# shared_pcb.net
KiCad netlist of a schematic drawn in EAGLE
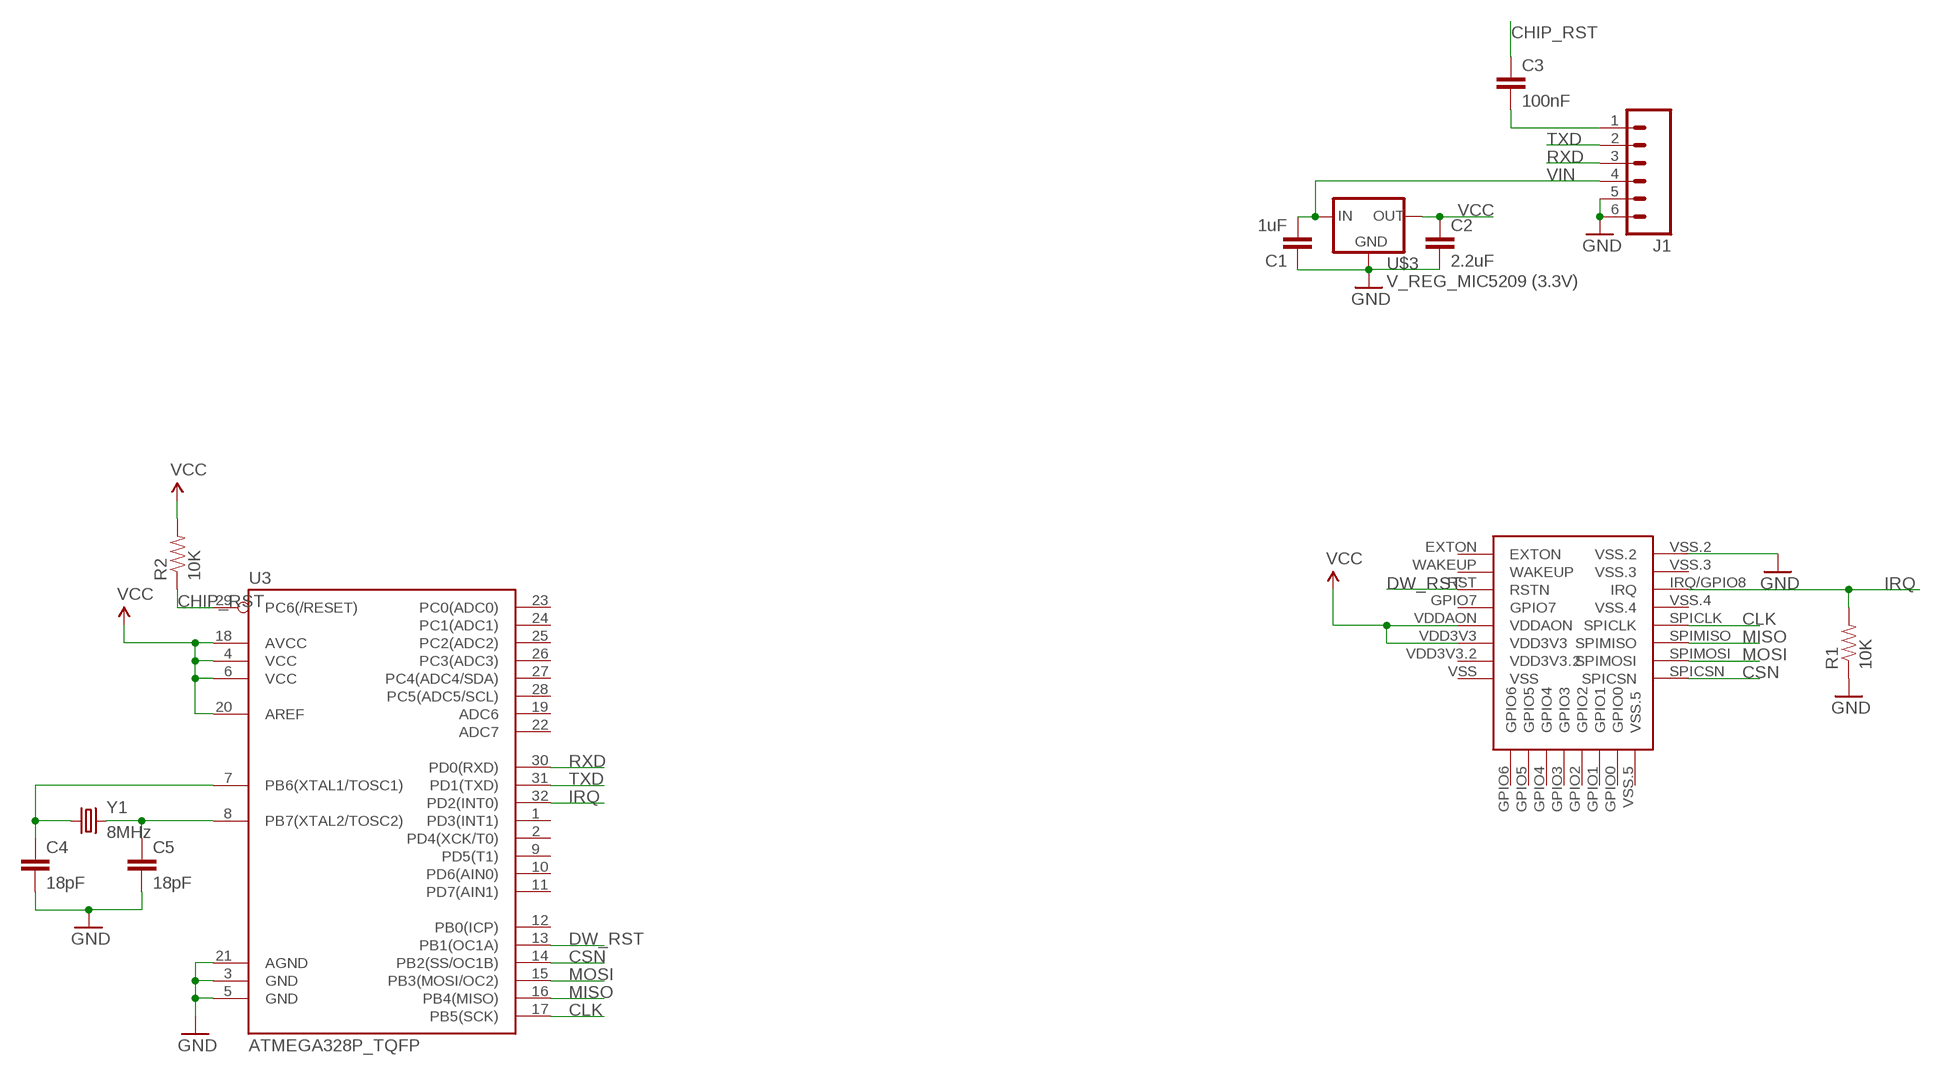
[diagram p0: schematic, sheet 1]

(export (version "E")
  (design (tool "Eeschema 10.0.6"))
  (components
    (comp (ref "C1")
      (value "1uF")
      (footprint "eagle-import:1206")
      (libsource (lib "eagle-import") (part "CAP1206"))
    )
    (comp (ref "C2")
      (value "2.2uF")
      (footprint "eagle-import:1206")
      (libsource (lib "eagle-import") (part "CAP1206"))
    )
    (comp (ref "C3")
      (value "100nF")
      (footprint "eagle-import:1206")
      (libsource (lib "eagle-import") (part "CAP1206"))
    )
    (comp (ref "C4")
      (value "18pF")
      (footprint "eagle-import:1206")
      (libsource (lib "eagle-import") (part "CAP1206"))
    )
    (comp (ref "C5")
      (value "18pF")
      (footprint "eagle-import:1206")
      (libsource (lib "eagle-import") (part "CAP1206"))
    )
    (comp (ref "J1")
      (value "M06LOCK")
      (footprint "eagle-import:1X06_LOCK")
      (libsource (lib "eagle-import") (part "M06LOCK"))
    )
    (comp (ref "R1")
      (value "10K")
      (footprint "eagle-import:1206")
      (libsource (lib "eagle-import") (part "RESISTOR1206"))
    )
    (comp (ref "R2")
      (value "10K")
      (footprint "eagle-import:1206")
      (libsource (lib "eagle-import") (part "RESISTOR1206"))
    )
    (comp (ref "U$1")
      (value "DWM1000")
      (footprint "eagle-import:DWM1000")
      (libsource (lib "eagle-import") (part "DWM1000"))
    )
    (comp (ref "U$3")
      (value "V_REG_MIC5209 (3.3V)")
      (footprint "eagle-import:SOT223")
      (libsource (lib "eagle-import") (part "V_REG_MIC2920"))
    )
    (comp (ref "U3")
      (value "ATMEGA328P_TQFP")
      (footprint "eagle-import:TQFP32-08")
      (libsource (lib "eagle-import") (part "ATMEGA328P_TQFP"))
    )
    (comp (ref "Y1")
      (value "8MHz")
      (footprint "eagle-import:CRYSTAL-TXC-7A")
      (libsource (lib "eagle-import") (part "CRYSTALTXC-7A"))
    )
  )
  (nets
    (net (code "1") (name "/CHIP_RST") (class "Default")
      (node (ref "C3") (pin "1") (pinfunction "1_1") (pintype "passive"))
      (node (ref "R2") (pin "1") (pinfunction "1_1") (pintype "passive"))
      (node (ref "U3") (pin "29") (pinfunction "PC6(/RESET)_29") (pintype "bidirectional"))
    )
    (net (code "2") (name "/CLK") (class "Default")
      (node (ref "U$1") (pin "SPICLK") (pinfunction "SPICLK_SPICLK") (pintype "bidirectional"))
      (node (ref "U3") (pin "17") (pinfunction "PB5(SCK)_17") (pintype "bidirectional"))
    )
    (net (code "3") (name "/CSN") (class "Default")
      (node (ref "U$1") (pin "SPICSN") (pinfunction "SPICSN_SPICSN") (pintype "bidirectional"))
      (node (ref "U3") (pin "14") (pinfunction "PB2(SS/OC1B)_14") (pintype "bidirectional"))
    )
    (net (code "4") (name "/DW_RST") (class "Default")
      (node (ref "U$1") (pin "RST") (pinfunction "RSTN_RST") (pintype "bidirectional"))
      (node (ref "U3") (pin "13") (pinfunction "PB1(OC1A)_13") (pintype "bidirectional"))
    )
    (net (code "5") (name "/IRQ") (class "Default")
      (node (ref "R1") (pin "2") (pinfunction "2_2") (pintype "passive"))
      (node (ref "U$1") (pin "IRQ/GPIO8") (pinfunction "IRQ_IRQ/GPIO8") (pintype "bidirectional"))
      (node (ref "U3") (pin "32") (pinfunction "PD2(INT0)_32") (pintype "bidirectional"))
    )
    (net (code "6") (name "/MISO") (class "Default")
      (node (ref "U$1") (pin "SPIMISO") (pinfunction "SPIMISO_SPIMISO") (pintype "bidirectional"))
      (node (ref "U3") (pin "16") (pinfunction "PB4(MISO)_16") (pintype "bidirectional"))
    )
    (net (code "7") (name "/MOSI") (class "Default")
      (node (ref "U$1") (pin "SPIMOSI") (pinfunction "SPIMOSI_SPIMOSI") (pintype "bidirectional"))
      (node (ref "U3") (pin "15") (pinfunction "PB3(MOSI/OC2)_15") (pintype "bidirectional"))
    )
    (net (code "8") (name "/RXD") (class "Default")
      (node (ref "J1") (pin "3") (pinfunction "3_3") (pintype "passive"))
      (node (ref "U3") (pin "30") (pinfunction "PD0(RXD)_30") (pintype "bidirectional"))
    )
    (net (code "9") (name "/TXD") (class "Default")
      (node (ref "J1") (pin "2") (pinfunction "2_2") (pintype "passive"))
      (node (ref "U3") (pin "31") (pinfunction "PD1(TXD)_31") (pintype "bidirectional"))
    )
    (net (code "10") (name "/VIN") (class "Default")
      (node (ref "C1") (pin "2") (pinfunction "2_2") (pintype "passive"))
      (node (ref "J1") (pin "4") (pinfunction "4_4") (pintype "passive"))
      (node (ref "U$3") (pin "1") (pinfunction "IN_1") (pintype "input"))
    )
    (net (code "11") (name "GND") (class "Default")
      (node (ref "C1") (pin "1") (pinfunction "1_1") (pintype "passive"))
      (node (ref "C2") (pin "2") (pinfunction "2_2") (pintype "passive"))
      (node (ref "C4") (pin "2") (pinfunction "2_2") (pintype "passive"))
      (node (ref "C5") (pin "2") (pinfunction "2_2") (pintype "passive"))
      (node (ref "J1") (pin "5") (pinfunction "5_5") (pintype "passive"))
      (node (ref "J1") (pin "6") (pinfunction "6_6") (pintype "passive"))
      (node (ref "R1") (pin "1") (pinfunction "1_1") (pintype "passive"))
      (node (ref "U$1") (pin "VSS.2") (pinfunction "VSS.2_VSS.2") (pintype "bidirectional"))
      (node (ref "U$3") (pin "2") (pinfunction "GND_2") (pintype "input"))
      (node (ref "U3") (pin "21") (pinfunction "AGND_21") (pintype "bidirectional"))
      (node (ref "U3") (pin "3") (pinfunction "GND_3") (pintype "bidirectional"))
      (node (ref "U3") (pin "5") (pinfunction "GND_5") (pintype "bidirectional"))
    )
    (net (code "12") (name "Net-(C3-Pad2)") (class "Default")
      (node (ref "C3") (pin "2") (pinfunction "2_2") (pintype "passive"))
      (node (ref "J1") (pin "1") (pinfunction "1_1") (pintype "passive"))
    )
    (net (code "13") (name "Net-(U3-PB6(XTAL1{slash}TOSC1))") (class "Default")
      (node (ref "C4") (pin "1") (pinfunction "1_1") (pintype "passive"))
      (node (ref "U3") (pin "7") (pinfunction "PB6(XTAL1/TOSC1)_7") (pintype "bidirectional"))
      (node (ref "Y1") (pin "P$1") (pinfunction "1_P$1") (pintype "passive"))
    )
    (net (code "14") (name "Net-(U3-PB7(XTAL2{slash}TOSC2))") (class "Default")
      (node (ref "C5") (pin "1") (pinfunction "1_1") (pintype "passive"))
      (node (ref "U3") (pin "8") (pinfunction "PB7(XTAL2/TOSC2)_8") (pintype "bidirectional"))
      (node (ref "Y1") (pin "P$2") (pinfunction "2_P$2") (pintype "passive"))
    )
    (net (code "15") (name "VCC") (class "Default")
      (node (ref "C2") (pin "1") (pinfunction "1_1") (pintype "passive"))
      (node (ref "R2") (pin "2") (pinfunction "2_2") (pintype "passive"))
      (node (ref "U$1") (pin "VDD3V3") (pinfunction "VDD3V3_VDD3V3") (pintype "bidirectional"))
      (node (ref "U$1") (pin "VDDAON") (pinfunction "VDDAON_VDDAON") (pintype "bidirectional"))
      (node (ref "U$3") (pin "3") (pinfunction "OUT_3") (pintype "passive"))
      (node (ref "U3") (pin "18") (pinfunction "AVCC_18") (pintype "bidirectional"))
      (node (ref "U3") (pin "20") (pinfunction "AREF_20") (pintype "bidirectional"))
      (node (ref "U3") (pin "4") (pinfunction "VCC_4") (pintype "bidirectional"))
      (node (ref "U3") (pin "6") (pinfunction "VCC_6") (pintype "bidirectional"))
    )
    (net (code "16") (name "unconnected-(U$1-PadEXTON)") (class "Default")
      (node (ref "U$1") (pin "EXTON") (pinfunction "EXTON_EXTON") (pintype "bidirectional"))
    )
    (net (code "17") (name "unconnected-(U$1-PadGPIO0)") (class "Default")
      (node (ref "U$1") (pin "GPIO0") (pinfunction "GPIO0_GPIO0") (pintype "bidirectional"))
    )
    (net (code "18") (name "unconnected-(U$1-PadGPIO1)") (class "Default")
      (node (ref "U$1") (pin "GPIO1") (pinfunction "GPIO1_GPIO1") (pintype "bidirectional"))
    )
    (net (code "19") (name "unconnected-(U$1-PadGPIO2)") (class "Default")
      (node (ref "U$1") (pin "GPIO2") (pinfunction "GPIO2_GPIO2") (pintype "bidirectional"))
    )
    (net (code "20") (name "unconnected-(U$1-PadGPIO3)") (class "Default")
      (node (ref "U$1") (pin "GPIO3") (pinfunction "GPIO3_GPIO3") (pintype "bidirectional"))
    )
    (net (code "21") (name "unconnected-(U$1-PadGPIO4)") (class "Default")
      (node (ref "U$1") (pin "GPIO4") (pinfunction "GPIO4_GPIO4") (pintype "bidirectional"))
    )
    (net (code "22") (name "unconnected-(U$1-PadGPIO5)") (class "Default")
      (node (ref "U$1") (pin "GPIO5") (pinfunction "GPIO5_GPIO5") (pintype "bidirectional"))
    )
    (net (code "23") (name "unconnected-(U$1-PadGPIO6)") (class "Default")
      (node (ref "U$1") (pin "GPIO6") (pinfunction "GPIO6_GPIO6") (pintype "bidirectional"))
    )
    (net (code "24") (name "unconnected-(U$1-PadGPIO7)") (class "Default")
      (node (ref "U$1") (pin "GPIO7") (pinfunction "GPIO7_GPIO7") (pintype "bidirectional"))
    )
    (net (code "25") (name "unconnected-(U$1-PadVDD3V3.2)") (class "Default")
      (node (ref "U$1") (pin "VDD3V3.2") (pinfunction "VDD3V3.2_VDD3V3.2") (pintype "bidirectional"))
    )
    (net (code "26") (name "unconnected-(U$1-PadVSS)") (class "Default")
      (node (ref "U$1") (pin "VSS") (pinfunction "VSS_VSS") (pintype "bidirectional"))
    )
    (net (code "27") (name "unconnected-(U$1-PadVSS.3)") (class "Default")
      (node (ref "U$1") (pin "VSS.3") (pinfunction "VSS.3_VSS.3") (pintype "bidirectional"))
    )
    (net (code "28") (name "unconnected-(U$1-PadVSS.4)") (class "Default")
      (node (ref "U$1") (pin "VSS.4") (pinfunction "VSS.4_VSS.4") (pintype "bidirectional"))
    )
    (net (code "29") (name "unconnected-(U$1-PadVSS.5)") (class "Default")
      (node (ref "U$1") (pin "VSS.5") (pinfunction "VSS.5_VSS.5") (pintype "bidirectional"))
    )
    (net (code "30") (name "unconnected-(U$1-PadWAKEUP)") (class "Default")
      (node (ref "U$1") (pin "WAKEUP") (pinfunction "WAKEUP_WAKEUP") (pintype "bidirectional"))
    )
    (net (code "31") (name "unconnected-(U3-ADC6-Pad19)") (class "Default")
      (node (ref "U3") (pin "19") (pinfunction "ADC6_19") (pintype "bidirectional"))
    )
    (net (code "32") (name "unconnected-(U3-ADC7-Pad22)") (class "Default")
      (node (ref "U3") (pin "22") (pinfunction "ADC7_22") (pintype "bidirectional"))
    )
    (net (code "33") (name "unconnected-(U3-PB0(ICP)-Pad12)") (class "Default")
      (node (ref "U3") (pin "12") (pinfunction "PB0(ICP)_12") (pintype "bidirectional"))
    )
    (net (code "34") (name "unconnected-(U3-PC0(ADC0)-Pad23)") (class "Default")
      (node (ref "U3") (pin "23") (pinfunction "PC0(ADC0)_23") (pintype "bidirectional"))
    )
    (net (code "35") (name "unconnected-(U3-PC1(ADC1)-Pad24)") (class "Default")
      (node (ref "U3") (pin "24") (pinfunction "PC1(ADC1)_24") (pintype "bidirectional"))
    )
    (net (code "36") (name "unconnected-(U3-PC2(ADC2)-Pad25)") (class "Default")
      (node (ref "U3") (pin "25") (pinfunction "PC2(ADC2)_25") (pintype "bidirectional"))
    )
    (net (code "37") (name "unconnected-(U3-PC3(ADC3)-Pad26)") (class "Default")
      (node (ref "U3") (pin "26") (pinfunction "PC3(ADC3)_26") (pintype "bidirectional"))
    )
    (net (code "38") (name "unconnected-(U3-PC4(ADC4{slash}SDA)-Pad27)") (class "Default")
      (node (ref "U3") (pin "27") (pinfunction "PC4(ADC4/SDA)_27") (pintype "bidirectional"))
    )
    (net (code "39") (name "unconnected-(U3-PC5(ADC5{slash}SCL)-Pad28)") (class "Default")
      (node (ref "U3") (pin "28") (pinfunction "PC5(ADC5/SCL)_28") (pintype "bidirectional"))
    )
    (net (code "40") (name "unconnected-(U3-PD3(INT1)-Pad1)") (class "Default")
      (node (ref "U3") (pin "1") (pinfunction "PD3(INT1)_1") (pintype "bidirectional"))
    )
    (net (code "41") (name "unconnected-(U3-PD4(XCK{slash}T0)-Pad2)") (class "Default")
      (node (ref "U3") (pin "2") (pinfunction "PD4(XCK/T0)_2") (pintype "bidirectional"))
    )
    (net (code "42") (name "unconnected-(U3-PD5(T1)-Pad9)") (class "Default")
      (node (ref "U3") (pin "9") (pinfunction "PD5(T1)_9") (pintype "bidirectional"))
    )
    (net (code "43") (name "unconnected-(U3-PD6(AIN0)-Pad10)") (class "Default")
      (node (ref "U3") (pin "10") (pinfunction "PD6(AIN0)_10") (pintype "bidirectional"))
    )
    (net (code "44") (name "unconnected-(U3-PD7(AIN1)-Pad11)") (class "Default")
      (node (ref "U3") (pin "11") (pinfunction "PD7(AIN1)_11") (pintype "bidirectional"))
    )
  )
)
